# SCH_Claysight-MK2.net
KiCad netlist of a schematic drawn in EasyEDA
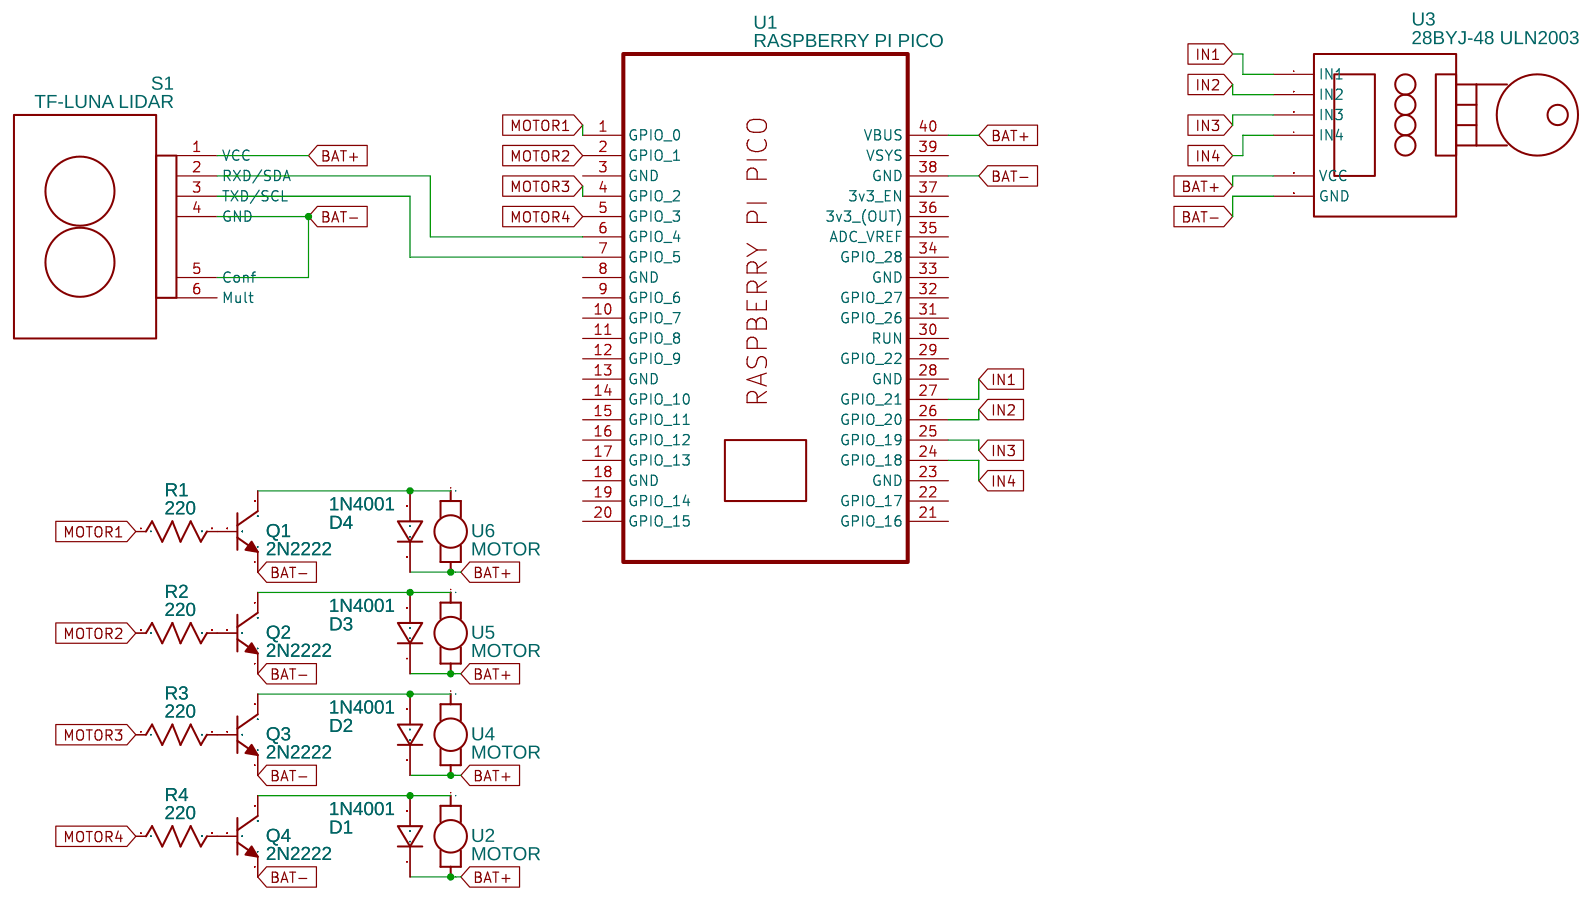
[diagram p0: schematic sheet]

(export (version "E")
  (design (tool "Eeschema 10.0.6"))
  (components
    (comp (ref "D1")
      (value "1N4001")
      (fields (field (name "BOM_Manufacturer Part") "1N4007W") (field (name "BOM_Supplier Part") "C328592"))
      (libsource (lib "") (part "1N4007W"))
    )
    (comp (ref "D2")
      (value "1N4001")
      (fields (field (name "BOM_Manufacturer Part") "1N4007W") (field (name "BOM_Supplier Part") "C328592"))
      (libsource (lib "") (part "1N4007W"))
    )
    (comp (ref "D3")
      (value "1N4001")
      (fields (field (name "BOM_Manufacturer Part") "1N4007W") (field (name "BOM_Supplier Part") "C328592"))
      (libsource (lib "") (part "1N4007W"))
    )
    (comp (ref "D4")
      (value "1N4001")
      (fields (field (name "BOM_Manufacturer Part") "1N4007W") (field (name "BOM_Supplier Part") "C328592"))
      (libsource (lib "") (part "1N4007W"))
    )
    (comp (ref "Q1")
      (value "2N2222")
      (fields
        (field (name "BOM_Manufacturer Part") "2n3904S-RTK/PS")
        (field (name "BOM_Supplier Part") "C18536")
      )
      (libsource (lib "") (part "2N3904(SOT-23)"))
    )
    (comp (ref "Q2")
      (value "2N2222")
      (fields
        (field (name "BOM_Manufacturer Part") "2n3904S-RTK/PS")
        (field (name "BOM_Supplier Part") "C18536")
      )
      (libsource (lib "") (part "2N3904(SOT-23)"))
    )
    (comp (ref "Q3")
      (value "2N2222")
      (fields
        (field (name "BOM_Manufacturer Part") "2n3904S-RTK/PS")
        (field (name "BOM_Supplier Part") "C18536")
      )
      (libsource (lib "") (part "2N3904(SOT-23)"))
    )
    (comp (ref "Q4")
      (value "2N2222")
      (fields
        (field (name "BOM_Manufacturer Part") "2n3904S-RTK/PS")
        (field (name "BOM_Supplier Part") "C18536")
      )
      (libsource (lib "") (part "2N3904(SOT-23)"))
    )
    (comp (ref "R1") (value "220") (libsource (lib "") (part "R_0603_US")))
    (comp (ref "R2") (value "220") (libsource (lib "") (part "R_0603_US")))
    (comp (ref "R3") (value "220") (libsource (lib "") (part "R_0603_US")))
    (comp (ref "R4") (value "220") (libsource (lib "") (part "R_0603_US")))
    (comp (ref "S1")
      (value "TF-LUNA LIDAR")
      (fields (field (name "BOM_Manufacturer Part") "TF-LUNA"))
      (libsource (lib "") (part "TF-LUNA"))
    )
    (comp (ref "U1") (value "RASPBERRY PI PICO") (libsource (lib "") (part "Raspberry Pi Pico W")))
    (comp (ref "U2") (value "MOTOR") (libsource (lib "") (part "MOTOR")))
    (comp (ref "U3") (value "28BYJ-48 ULN2003") (libsource (lib "") (part "28BYJ-48 ULN2003")))
    (comp (ref "U4") (value "MOTOR") (libsource (lib "") (part "MOTOR")))
    (comp (ref "U5") (value "MOTOR") (libsource (lib "") (part "MOTOR")))
    (comp (ref "U6") (value "MOTOR") (libsource (lib "") (part "MOTOR")))
  )
  (nets
    (net (code "1") (name "BAT+") (class "Default")
      (node (ref "D1") (pin "1") (pinfunction "1_1") (pintype "unspecified"))
      (node (ref "D2") (pin "1") (pinfunction "1_1") (pintype "unspecified"))
      (node (ref "D3") (pin "1") (pinfunction "1_1") (pintype "unspecified"))
      (node (ref "D4") (pin "1") (pinfunction "1_1") (pintype "unspecified"))
      (node (ref "U1") (pin "40") (pinfunction "VBUS_40") (pintype "unspecified"))
      (node (ref "U2") (pin "-") (pinfunction "-_-") (pintype "unspecified"))
      (node (ref "U3") (pin "5") (pinfunction "VCC_5") (pintype "unspecified"))
      (node (ref "U4") (pin "-") (pinfunction "-_-") (pintype "unspecified"))
      (node (ref "U5") (pin "-") (pinfunction "-_-") (pintype "unspecified"))
      (node (ref "U6") (pin "-") (pinfunction "-_-") (pintype "unspecified"))
    )
    (net (code "2") (name "BAT-") (class "Default")
      (node (ref "Q1") (pin "1") (pinfunction "E_1") (pintype "input"))
      (node (ref "Q2") (pin "1") (pinfunction "E_1") (pintype "input"))
      (node (ref "Q3") (pin "1") (pinfunction "E_1") (pintype "input"))
      (node (ref "Q4") (pin "1") (pinfunction "E_1") (pintype "input"))
      (node (ref "U1") (pin "38") (pinfunction "GND_38") (pintype "unspecified"))
      (node (ref "U3") (pin "6") (pinfunction "GND_6") (pintype "unspecified"))
    )
    (net (code "3") (name "IN1") (class "Default")
      (node (ref "U1") (pin "27") (pinfunction "GPIO_21_27") (pintype "unspecified"))
      (node (ref "U3") (pin "1") (pinfunction "IN1_1") (pintype "unspecified"))
    )
    (net (code "4") (name "IN2") (class "Default")
      (node (ref "U1") (pin "26") (pinfunction "GPIO_20_26") (pintype "unspecified"))
      (node (ref "U3") (pin "2") (pinfunction "IN2_2") (pintype "unspecified"))
    )
    (net (code "5") (name "IN3") (class "Default")
      (node (ref "U1") (pin "25") (pinfunction "GPIO_19_25") (pintype "unspecified"))
      (node (ref "U3") (pin "3") (pinfunction "IN3_3") (pintype "unspecified"))
    )
    (net (code "6") (name "IN4") (class "Default")
      (node (ref "U1") (pin "24") (pinfunction "GPIO_18_24") (pintype "unspecified"))
      (node (ref "U3") (pin "4") (pinfunction "IN4_4") (pintype "unspecified"))
    )
    (net (code "7") (name "MOTOR1") (class "Default")
      (node (ref "R1") (pin "1") (pinfunction "1_1") (pintype "unspecified"))
      (node (ref "U1") (pin "1") (pinfunction "GPIO_0_1") (pintype "unspecified"))
    )
    (net (code "8") (name "MOTOR2") (class "Default")
      (node (ref "R2") (pin "1") (pinfunction "1_1") (pintype "unspecified"))
      (node (ref "U1") (pin "2") (pinfunction "GPIO_1_2") (pintype "unspecified"))
    )
    (net (code "9") (name "MOTOR3") (class "Default")
      (node (ref "R3") (pin "1") (pinfunction "1_1") (pintype "unspecified"))
      (node (ref "U1") (pin "4") (pinfunction "GPIO_2_4") (pintype "unspecified"))
    )
    (net (code "10") (name "MOTOR4") (class "Default")
      (node (ref "R4") (pin "1") (pinfunction "1_1") (pintype "unspecified"))
      (node (ref "U1") (pin "5") (pinfunction "GPIO_3_5") (pintype "unspecified"))
    )
    (net (code "11") (name "Net-(Q1-B)") (class "Default")
      (node (ref "Q1") (pin "2") (pinfunction "B_2") (pintype "input"))
      (node (ref "R1") (pin "2") (pinfunction "2_2") (pintype "unspecified"))
    )
    (net (code "12") (name "Net-(Q1-C)") (class "Default")
      (node (ref "D4") (pin "2") (pinfunction "2_2") (pintype "unspecified"))
      (node (ref "Q1") (pin "3") (pinfunction "C_3") (pintype "input"))
      (node (ref "U6") (pin "+") (pinfunction "+_+") (pintype "unspecified"))
    )
    (net (code "13") (name "Net-(Q2-B)") (class "Default")
      (node (ref "Q2") (pin "2") (pinfunction "B_2") (pintype "input"))
      (node (ref "R2") (pin "2") (pinfunction "2_2") (pintype "unspecified"))
    )
    (net (code "14") (name "Net-(Q2-C)") (class "Default")
      (node (ref "D3") (pin "2") (pinfunction "2_2") (pintype "unspecified"))
      (node (ref "Q2") (pin "3") (pinfunction "C_3") (pintype "input"))
      (node (ref "U5") (pin "+") (pinfunction "+_+") (pintype "unspecified"))
    )
    (net (code "15") (name "Net-(Q3-B)") (class "Default")
      (node (ref "Q3") (pin "2") (pinfunction "B_2") (pintype "input"))
      (node (ref "R3") (pin "2") (pinfunction "2_2") (pintype "unspecified"))
    )
    (net (code "16") (name "Net-(Q3-C)") (class "Default")
      (node (ref "D2") (pin "2") (pinfunction "2_2") (pintype "unspecified"))
      (node (ref "Q3") (pin "3") (pinfunction "C_3") (pintype "input"))
      (node (ref "U4") (pin "+") (pinfunction "+_+") (pintype "unspecified"))
    )
    (net (code "17") (name "Net-(Q4-B)") (class "Default")
      (node (ref "Q4") (pin "2") (pinfunction "B_2") (pintype "input"))
      (node (ref "R4") (pin "2") (pinfunction "2_2") (pintype "unspecified"))
    )
    (net (code "18") (name "Net-(Q4-C)") (class "Default")
      (node (ref "D1") (pin "2") (pinfunction "2_2") (pintype "unspecified"))
      (node (ref "Q4") (pin "3") (pinfunction "C_3") (pintype "input"))
      (node (ref "U2") (pin "+") (pinfunction "+_+") (pintype "unspecified"))
    )
    (net (code "19") (name "unconnected-(S1-Conf-Pad5)") (class "Default")
      (node (ref "S1") (pin "5") (pinfunction "Conf_5") (pintype "unspecified"))
    )
    (net (code "20") (name "unconnected-(S1-GND-Pad4)") (class "Default")
      (node (ref "S1") (pin "4") (pinfunction "GND_4") (pintype "unspecified"))
    )
    (net (code "21") (name "unconnected-(S1-Mult-Pad6)") (class "Default")
      (node (ref "S1") (pin "6") (pinfunction "Mult_6") (pintype "unspecified"))
    )
    (net (code "22") (name "unconnected-(S1-RXD{slash}SDA-Pad2)") (class "Default")
      (node (ref "S1") (pin "2") (pinfunction "RXD/SDA_2") (pintype "unspecified"))
    )
    (net (code "23") (name "unconnected-(S1-TXD{slash}SCL-Pad3)") (class "Default")
      (node (ref "S1") (pin "3") (pinfunction "TXD/SCL_3") (pintype "unspecified"))
    )
    (net (code "24") (name "unconnected-(S1-VCC-Pad1)") (class "Default")
      (node (ref "S1") (pin "1") (pinfunction "VCC_1") (pintype "unspecified"))
    )
    (net (code "25") (name "unconnected-(U1-3v3_(OUT)-Pad36)") (class "Default")
      (node (ref "U1") (pin "36") (pinfunction "3v3_(OUT)_36") (pintype "unspecified"))
    )
    (net (code "26") (name "unconnected-(U1-3v3_EN-Pad37)") (class "Default")
      (node (ref "U1") (pin "37") (pinfunction "3v3_EN_37") (pintype "unspecified"))
    )
    (net (code "27") (name "unconnected-(U1-ADC_VREF-Pad35)") (class "Default")
      (node (ref "U1") (pin "35") (pinfunction "ADC_VREF_35") (pintype "unspecified"))
    )
    (net (code "28") (name "unconnected-(U1-GND-Pad3)") (class "Default")
      (node (ref "U1") (pin "3") (pinfunction "GND_3") (pintype "unspecified"))
    )
    (net (code "29") (name "unconnected-(U1-GND-Pad8)") (class "Default")
      (node (ref "U1") (pin "8") (pinfunction "GND_8") (pintype "unspecified"))
    )
    (net (code "30") (name "unconnected-(U1-GND-Pad13)") (class "Default")
      (node (ref "U1") (pin "13") (pinfunction "GND_13") (pintype "unspecified"))
    )
    (net (code "31") (name "unconnected-(U1-GND-Pad18)") (class "Default")
      (node (ref "U1") (pin "18") (pinfunction "GND_18") (pintype "unspecified"))
    )
    (net (code "32") (name "unconnected-(U1-GND-Pad23)") (class "Default")
      (node (ref "U1") (pin "23") (pinfunction "GND_23") (pintype "unspecified"))
    )
    (net (code "33") (name "unconnected-(U1-GND-Pad28)") (class "Default")
      (node (ref "U1") (pin "28") (pinfunction "GND_28") (pintype "unspecified"))
    )
    (net (code "34") (name "unconnected-(U1-GND-Pad33)") (class "Default")
      (node (ref "U1") (pin "33") (pinfunction "GND_33") (pintype "unspecified"))
    )
    (net (code "35") (name "unconnected-(U1-GPIO_4-Pad6)") (class "Default")
      (node (ref "U1") (pin "6") (pinfunction "GPIO_4_6") (pintype "unspecified"))
    )
    (net (code "36") (name "unconnected-(U1-GPIO_5-Pad7)") (class "Default")
      (node (ref "U1") (pin "7") (pinfunction "GPIO_5_7") (pintype "unspecified"))
    )
    (net (code "37") (name "unconnected-(U1-GPIO_6-Pad9)") (class "Default")
      (node (ref "U1") (pin "9") (pinfunction "GPIO_6_9") (pintype "unspecified"))
    )
    (net (code "38") (name "unconnected-(U1-GPIO_7-Pad10)") (class "Default")
      (node (ref "U1") (pin "10") (pinfunction "GPIO_7_10") (pintype "unspecified"))
    )
    (net (code "39") (name "unconnected-(U1-GPIO_8-Pad11)") (class "Default")
      (node (ref "U1") (pin "11") (pinfunction "GPIO_8_11") (pintype "unspecified"))
    )
    (net (code "40") (name "unconnected-(U1-GPIO_9-Pad12)") (class "Default")
      (node (ref "U1") (pin "12") (pinfunction "GPIO_9_12") (pintype "unspecified"))
    )
    (net (code "41") (name "unconnected-(U1-GPIO_10-Pad14)") (class "Default")
      (node (ref "U1") (pin "14") (pinfunction "GPIO_10_14") (pintype "unspecified"))
    )
    (net (code "42") (name "unconnected-(U1-GPIO_11-Pad15)") (class "Default")
      (node (ref "U1") (pin "15") (pinfunction "GPIO_11_15") (pintype "unspecified"))
    )
    (net (code "43") (name "unconnected-(U1-GPIO_12-Pad16)") (class "Default")
      (node (ref "U1") (pin "16") (pinfunction "GPIO_12_16") (pintype "unspecified"))
    )
    (net (code "44") (name "unconnected-(U1-GPIO_13-Pad17)") (class "Default")
      (node (ref "U1") (pin "17") (pinfunction "GPIO_13_17") (pintype "unspecified"))
    )
    (net (code "45") (name "unconnected-(U1-GPIO_14-Pad19)") (class "Default")
      (node (ref "U1") (pin "19") (pinfunction "GPIO_14_19") (pintype "unspecified"))
    )
    (net (code "46") (name "unconnected-(U1-GPIO_15-Pad20)") (class "Default")
      (node (ref "U1") (pin "20") (pinfunction "GPIO_15_20") (pintype "unspecified"))
    )
    (net (code "47") (name "unconnected-(U1-GPIO_16-Pad21)") (class "Default")
      (node (ref "U1") (pin "21") (pinfunction "GPIO_16_21") (pintype "unspecified"))
    )
    (net (code "48") (name "unconnected-(U1-GPIO_17-Pad22)") (class "Default")
      (node (ref "U1") (pin "22") (pinfunction "GPIO_17_22") (pintype "unspecified"))
    )
    (net (code "49") (name "unconnected-(U1-GPIO_22-Pad29)") (class "Default")
      (node (ref "U1") (pin "29") (pinfunction "GPIO_22_29") (pintype "unspecified"))
    )
    (net (code "50") (name "unconnected-(U1-GPIO_26-Pad31)") (class "Default")
      (node (ref "U1") (pin "31") (pinfunction "GPIO_26_31") (pintype "unspecified"))
    )
    (net (code "51") (name "unconnected-(U1-GPIO_27-Pad32)") (class "Default")
      (node (ref "U1") (pin "32") (pinfunction "GPIO_27_32") (pintype "unspecified"))
    )
    (net (code "52") (name "unconnected-(U1-GPIO_28-Pad34)") (class "Default")
      (node (ref "U1") (pin "34") (pinfunction "GPIO_28_34") (pintype "unspecified"))
    )
    (net (code "53") (name "unconnected-(U1-RUN-Pad30)") (class "Default")
      (node (ref "U1") (pin "30") (pinfunction "RUN_30") (pintype "unspecified"))
    )
    (net (code "54") (name "unconnected-(U1-VSYS-Pad39)") (class "Default")
      (node (ref "U1") (pin "39") (pinfunction "VSYS_39") (pintype "unspecified"))
    )
  )
)
